# 2_TSAL.net
KiCad netlist of a schematic drawn in Altium Designer
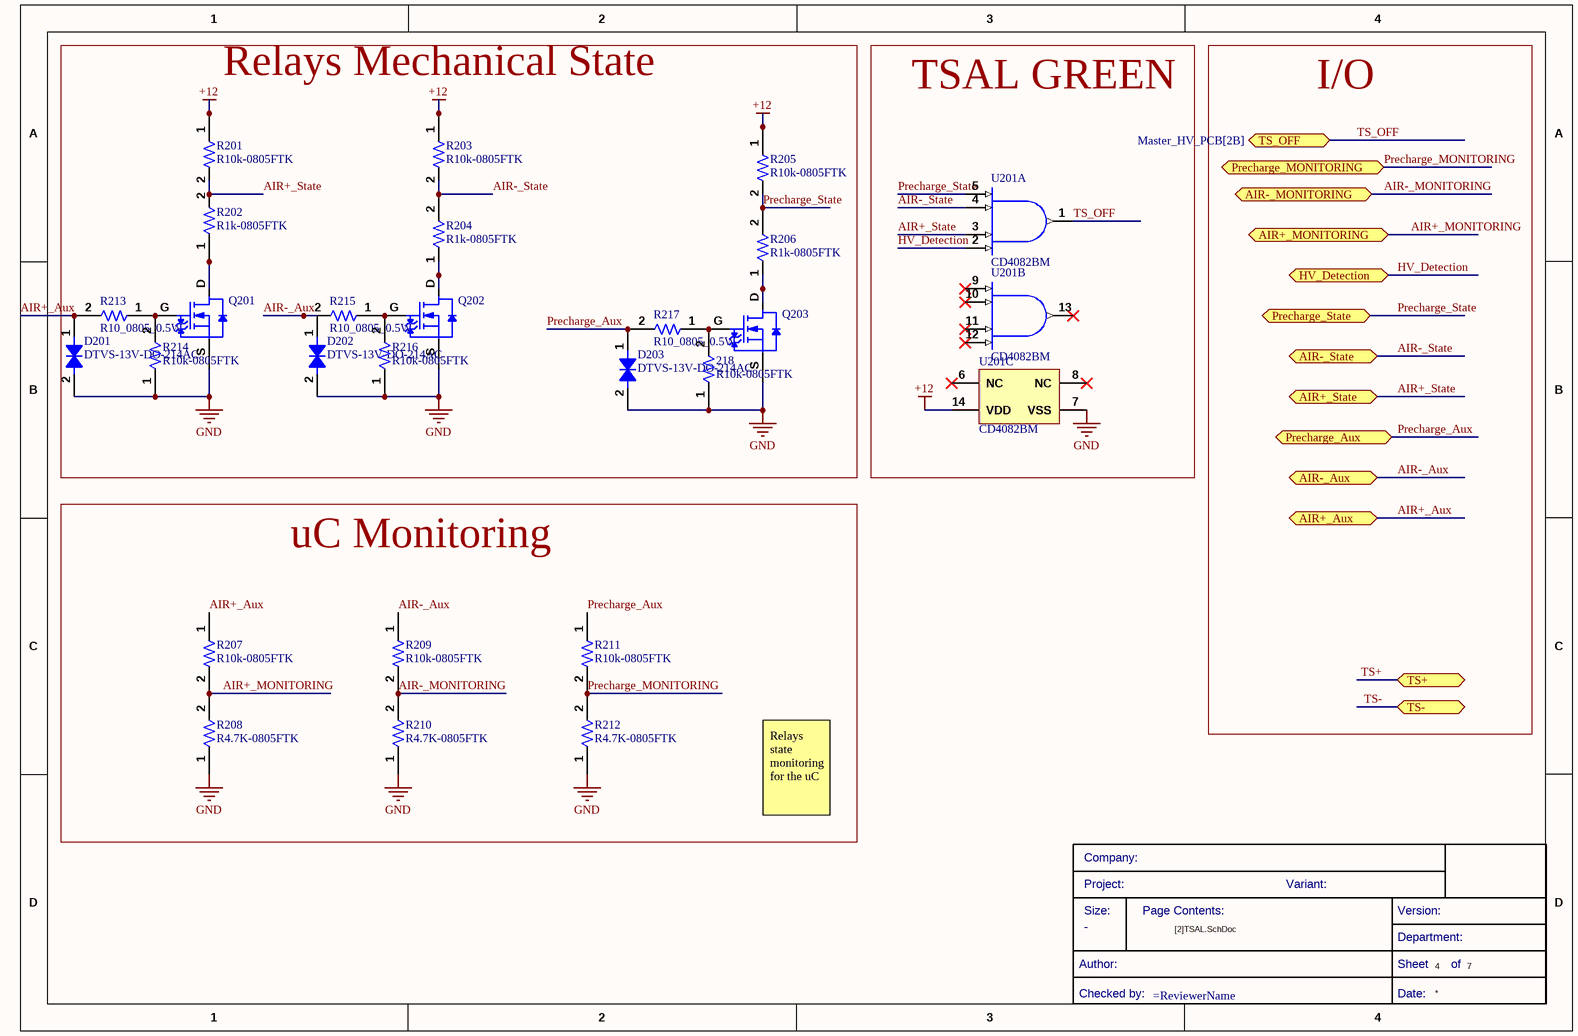
[diagram p0: [2]TSAL.SchDoc]

(export (version "E")
  (design (tool "Eeschema 10.0.6"))
  (components
    (comp (ref "218")
      (value "R10k-0805FTK")
      (footprint "R0805FTK")
      (fields (field (name "TOLERANCE") "5%") (field (name ".CREATOR") "DR"))
      (libsource (lib "EMEA- E-Tech Racing- I'Escola d'Enginyeria de Barcelona Est") (part "R"))
    )
    (comp (ref "D201")
      (value "DTVS-13V-DO-214AC")
      (footprint "DTVS-DO-214AC")
      (description "Tvs Diode, 400W, 13V, Bidir, DO-214AC")
      (fields
        (field (name "MANUFACTURER PART NUMBER") "824501131")
        (field (name "MANUFACTURER") "Wurth Electronics")
        (field (name ".CREATOR") "DO")
      )
      (libsource (lib "EMEA- E-Tech Racing- I'Escola d'Enginyeria de Barcelona Est") (part "DTVS-BD-30k-SOD323"))
    )
    (comp (ref "D202")
      (value "DTVS-13V-DO-214AC")
      (footprint "DTVS-DO-214AC")
      (description "Tvs Diode, 400W, 13V, Bidir, DO-214AC")
      (fields
        (field (name "MANUFACTURER PART NUMBER") "824501131")
        (field (name "MANUFACTURER") "Wurth Electronics")
        (field (name ".CREATOR") "DO")
      )
      (libsource (lib "EMEA- E-Tech Racing- I'Escola d'Enginyeria de Barcelona Est") (part "DTVS-BD-30k-SOD323"))
    )
    (comp (ref "D203")
      (value "DTVS-13V-DO-214AC")
      (footprint "DTVS-DO-214AC")
      (description "Tvs Diode, 400W, 13V, Bidir, DO-214AC")
      (fields
        (field (name "MANUFACTURER PART NUMBER") "824501131")
        (field (name "MANUFACTURER") "Wurth Electronics")
        (field (name ".CREATOR") "DO")
      )
      (libsource (lib "EMEA- E-Tech Racing- I'Escola d'Enginyeria de Barcelona Est") (part "DTVS-BD-30k-SOD323"))
    )
    (comp (ref "Q201")
      (value "SQ2362ES-T1_BE3")
      (footprint "SOT95P245X110-3N")
      (description "Small Signal Field-Effect Transistor")
      (libsource (lib "EMEA- E-Tech Racing- I'Escola d'Enginyeria de Barcelona Est") (part "TRT-NCH-3/35-CPH"))
    )
    (comp (ref "Q202")
      (value "SQ2362ES-T1_BE3")
      (footprint "SOT95P245X110-3N")
      (description "Small Signal Field-Effect Transistor")
      (libsource (lib "EMEA- E-Tech Racing- I'Escola d'Enginyeria de Barcelona Est") (part "TRT-NCH-3/35-CPH"))
    )
    (comp (ref "Q203")
      (value "SQ2362ES-T1_BE3")
      (footprint "SOT95P245X110-3N")
      (description "Small Signal Field-Effect Transistor")
      (libsource (lib "EMEA- E-Tech Racing- I'Escola d'Enginyeria de Barcelona Est") (part "TRT-NCH-3/35-CPH"))
    )
    (comp (ref "R201")
      (value "R10k-0805FTK")
      (footprint "R0805FTK")
      (fields (field (name "TOLERANCE") "5%") (field (name ".CREATOR") "DR"))
      (libsource (lib "EMEA- E-Tech Racing- I'Escola d'Enginyeria de Barcelona Est") (part "R9.09K-1206FTK"))
    )
    (comp (ref "R202")
      (value "R1k-0805FTK")
      (footprint "R0805FTK")
      (description "Res Thick Film 0805 1K Ohm 5% 1/8W ±200ppm/°C Molded SMD SMD Paper Tape on Plastic Reel")
      (fields (field (name "TOLERANCE") "5%") (field (name ".CREATOR") "GP"))
      (libsource (lib "EMEA- E-Tech Racing- I'Escola d'Enginyeria de Barcelona Est") (part "R9.09K-1206FTK"))
    )
    (comp (ref "R203")
      (value "R10k-0805FTK")
      (footprint "R0805FTK")
      (fields (field (name "TOLERANCE") "5%") (field (name ".CREATOR") "DR"))
      (libsource (lib "EMEA- E-Tech Racing- I'Escola d'Enginyeria de Barcelona Est") (part "R9.09K-1206FTK"))
    )
    (comp (ref "R204")
      (value "R1k-0805FTK")
      (footprint "R0805FTK")
      (description "Res Thick Film 0805 1K Ohm 5% 1/8W ±200ppm/°C Molded SMD SMD Paper Tape on Plastic Reel")
      (fields (field (name "TOLERANCE") "5%") (field (name ".CREATOR") "GP"))
      (libsource (lib "EMEA- E-Tech Racing- I'Escola d'Enginyeria de Barcelona Est") (part "R9.09K-1206FTK"))
    )
    (comp (ref "R205")
      (value "R10k-0805FTK")
      (footprint "R0805FTK")
      (fields (field (name "TOLERANCE") "5%") (field (name ".CREATOR") "DR"))
      (libsource (lib "EMEA- E-Tech Racing- I'Escola d'Enginyeria de Barcelona Est") (part "R9.09K-1206FTK"))
    )
    (comp (ref "R206")
      (value "R1k-0805FTK")
      (footprint "R0805FTK")
      (description "Res Thick Film 0805 1K Ohm 5% 1/8W ±200ppm/°C Molded SMD SMD Paper Tape on Plastic Reel")
      (fields (field (name "TOLERANCE") "5%") (field (name ".CREATOR") "GP"))
      (libsource (lib "EMEA- E-Tech Racing- I'Escola d'Enginyeria de Barcelona Est") (part "R9.09K-1206FTK"))
    )
    (comp (ref "R207")
      (value "R10k-0805FTK")
      (footprint "R0805FTK")
      (fields (field (name "TOLERANCE") "5%") (field (name ".CREATOR") "DR"))
      (libsource (lib "EMEA- E-Tech Racing- I'Escola d'Enginyeria de Barcelona Est") (part "R9.09K-1206FTK"))
    )
    (comp (ref "R208")
      (value "R4.7K-0805FTK")
      (footprint "R0805FTK")
      (description "Res Thick Film 0805 4.7K Ohm 5% 1/8W ±200ppm/°C Molded SMD SMD Paper Tape on Plastic Reel")
      (fields (field (name "TOLERANCE") "5%") (field (name ".CREATOR") "DR"))
      (libsource (lib "EMEA- E-Tech Racing- I'Escola d'Enginyeria de Barcelona Est") (part "R9.09K-1206FTK"))
    )
    (comp (ref "R209")
      (value "R10k-0805FTK")
      (footprint "R0805FTK")
      (fields (field (name "TOLERANCE") "5%") (field (name ".CREATOR") "DR"))
      (libsource (lib "EMEA- E-Tech Racing- I'Escola d'Enginyeria de Barcelona Est") (part "R9.09K-1206FTK"))
    )
    (comp (ref "R210")
      (value "R4.7K-0805FTK")
      (footprint "R0805FTK")
      (description "Res Thick Film 0805 4.7K Ohm 5% 1/8W ±200ppm/°C Molded SMD SMD Paper Tape on Plastic Reel")
      (fields (field (name "TOLERANCE") "5%") (field (name ".CREATOR") "DR"))
      (libsource (lib "EMEA- E-Tech Racing- I'Escola d'Enginyeria de Barcelona Est") (part "R9.09K-1206FTK"))
    )
    (comp (ref "R211")
      (value "R10k-0805FTK")
      (footprint "R0805FTK")
      (fields (field (name "TOLERANCE") "5%") (field (name ".CREATOR") "DR"))
      (libsource (lib "EMEA- E-Tech Racing- I'Escola d'Enginyeria de Barcelona Est") (part "R9.09K-1206FTK"))
    )
    (comp (ref "R212")
      (value "R4.7K-0805FTK")
      (footprint "R0805FTK")
      (description "Res Thick Film 0805 4.7K Ohm 5% 1/8W ±200ppm/°C Molded SMD SMD Paper Tape on Plastic Reel")
      (fields (field (name "TOLERANCE") "5%") (field (name ".CREATOR") "DR"))
      (libsource (lib "EMEA- E-Tech Racing- I'Escola d'Enginyeria de Barcelona Est") (part "R9.09K-1206FTK"))
    )
    (comp (ref "R213")
      (value "R10_0805_0.5W")
      (footprint "0805")
      (fields (field (name "TOLERANCE") "1%") (field (name "POWER") "500mW"))
      (libsource (lib "EMEA- E-Tech Racing- I'Escola d'Enginyeria de Barcelona Est") (part "R9.09K-1206FTK"))
    )
    (comp (ref "R214")
      (value "R10k-0805FTK")
      (footprint "R0805FTK")
      (fields (field (name "TOLERANCE") "5%") (field (name ".CREATOR") "DR"))
      (libsource (lib "EMEA- E-Tech Racing- I'Escola d'Enginyeria de Barcelona Est") (part "R"))
    )
    (comp (ref "R215")
      (value "R10_0805_0.5W")
      (footprint "0805")
      (fields (field (name "TOLERANCE") "1%") (field (name "POWER") "500mW"))
      (libsource (lib "EMEA- E-Tech Racing- I'Escola d'Enginyeria de Barcelona Est") (part "R9.09K-1206FTK"))
    )
    (comp (ref "R216")
      (value "R10k-0805FTK")
      (footprint "R0805FTK")
      (fields (field (name "TOLERANCE") "5%") (field (name ".CREATOR") "DR"))
      (libsource (lib "EMEA- E-Tech Racing- I'Escola d'Enginyeria de Barcelona Est") (part "R"))
    )
    (comp (ref "R217")
      (value "R10_0805_0.5W")
      (footprint "0805")
      (fields (field (name "TOLERANCE") "1%") (field (name "POWER") "500mW"))
      (libsource (lib "EMEA- E-Tech Racing- I'Escola d'Enginyeria de Barcelona Est") (part "R9.09K-1206FTK"))
    )
    (comp (ref "U201")
      (value "CD4082BM")
      (footprint "D0014A_N")
      (description "AND Gate, 4000/14000/40000 Series, 2-Func, 4-Input, CMOS, PDSO14")
      (libsource (lib "EMEA- E-Tech Racing- I'Escola d'Enginyeria de Barcelona Est") (part "TI-CD4082B-14"))
    )
  )
  (nets
    (net (code "1") (name "+12") (class "Default")
      (node (ref "R201") (pin "1") (pinfunction "1_1") (pintype "passive"))
      (node (ref "R203") (pin "1") (pinfunction "1_1") (pintype "passive"))
      (node (ref "R205") (pin "1") (pinfunction "1_1") (pintype "passive"))
      (node (ref "U201") (pin "14") (pinfunction "VDD_14") (pintype "power_in"))
    )
    (net (code "2") (name "/AIR+_Aux") (class "Default")
      (node (ref "D201") (pin "1") (pinfunction "1_1") (pintype "passive"))
      (node (ref "R207") (pin "1") (pinfunction "1_1") (pintype "passive"))
      (node (ref "R213") (pin "2") (pinfunction "2_2") (pintype "passive"))
    )
    (net (code "3") (name "/AIR+_MONITORING") (class "Default")
      (node (ref "R207") (pin "2") (pinfunction "2_2") (pintype "passive"))
      (node (ref "R208") (pin "2") (pinfunction "2_2") (pintype "passive"))
    )
    (net (code "4") (name "/AIR+_State") (class "Default")
      (node (ref "R201") (pin "2") (pinfunction "2_2") (pintype "passive"))
      (node (ref "R202") (pin "2") (pinfunction "2_2") (pintype "passive"))
      (node (ref "U201") (pin "3") (pinfunction "C_3") (pintype "input"))
    )
    (net (code "5") (name "/AIR-_Aux") (class "Default")
      (node (ref "D202") (pin "1") (pinfunction "1_1") (pintype "passive"))
      (node (ref "R209") (pin "1") (pinfunction "1_1") (pintype "passive"))
      (node (ref "R215") (pin "2") (pinfunction "2_2") (pintype "passive"))
    )
    (net (code "6") (name "/AIR-_MONITORING") (class "Default")
      (node (ref "R209") (pin "2") (pinfunction "2_2") (pintype "passive"))
      (node (ref "R210") (pin "2") (pinfunction "2_2") (pintype "passive"))
    )
    (net (code "7") (name "/AIR-_State") (class "Default")
      (node (ref "R203") (pin "2") (pinfunction "2_2") (pintype "passive"))
      (node (ref "R204") (pin "2") (pinfunction "2_2") (pintype "passive"))
      (node (ref "U201") (pin "4") (pinfunction "B_4") (pintype "input"))
    )
    (net (code "8") (name "/HV_Detection") (class "Default")
      (node (ref "U201") (pin "2") (pinfunction "D_2") (pintype "input"))
    )
    (net (code "9") (name "/Precharge_Aux") (class "Default")
      (node (ref "D203") (pin "1") (pinfunction "1_1") (pintype "passive"))
      (node (ref "R211") (pin "1") (pinfunction "1_1") (pintype "passive"))
      (node (ref "R217") (pin "2") (pinfunction "2_2") (pintype "passive"))
    )
    (net (code "10") (name "/Precharge_MONITORING") (class "Default")
      (node (ref "R211") (pin "2") (pinfunction "2_2") (pintype "passive"))
      (node (ref "R212") (pin "2") (pinfunction "2_2") (pintype "passive"))
    )
    (net (code "11") (name "/Precharge_State") (class "Default")
      (node (ref "R205") (pin "2") (pinfunction "2_2") (pintype "passive"))
      (node (ref "R206") (pin "2") (pinfunction "2_2") (pintype "passive"))
      (node (ref "U201") (pin "5") (pinfunction "A_5") (pintype "input"))
    )
    (net (code "14") (name "/TS_OFF") (class "Default")
      (node (ref "U201") (pin "1") (pinfunction "J_1") (pintype "output"))
    )
    (net (code "15") (name "GND") (class "Default")
      (node (ref "218") (pin "1") (pinfunction "1_1") (pintype "passive"))
      (node (ref "D201") (pin "2") (pinfunction "2_2") (pintype "passive"))
      (node (ref "D202") (pin "2") (pinfunction "2_2") (pintype "passive"))
      (node (ref "D203") (pin "2") (pinfunction "2_2") (pintype "passive"))
      (node (ref "Q201") (pin "S") (pinfunction "S_S") (pintype "passive"))
      (node (ref "Q202") (pin "S") (pinfunction "S_S") (pintype "passive"))
      (node (ref "Q203") (pin "S") (pinfunction "S_S") (pintype "passive"))
      (node (ref "R208") (pin "1") (pinfunction "1_1") (pintype "passive"))
      (node (ref "R210") (pin "1") (pinfunction "1_1") (pintype "passive"))
      (node (ref "R212") (pin "1") (pinfunction "1_1") (pintype "passive"))
      (node (ref "R214") (pin "1") (pinfunction "1_1") (pintype "passive"))
      (node (ref "R216") (pin "1") (pinfunction "1_1") (pintype "passive"))
      (node (ref "U201") (pin "7") (pinfunction "VSS_7") (pintype "power_in"))
    )
    (net (code "16") (name "Net-(218-Pad2)") (class "Default")
      (node (ref "218") (pin "2") (pinfunction "2_2") (pintype "passive"))
      (node (ref "Q203") (pin "G") (pinfunction "G_G") (pintype "passive"))
      (node (ref "R217") (pin "1") (pinfunction "1_1") (pintype "passive"))
    )
    (net (code "17") (name "Net-(Q201-PadD)") (class "Default")
      (node (ref "Q201") (pin "D") (pinfunction "D_D") (pintype "passive"))
      (node (ref "R202") (pin "1") (pinfunction "1_1") (pintype "passive"))
    )
    (net (code "18") (name "Net-(Q201-PadG)") (class "Default")
      (node (ref "Q201") (pin "G") (pinfunction "G_G") (pintype "passive"))
      (node (ref "R213") (pin "1") (pinfunction "1_1") (pintype "passive"))
      (node (ref "R214") (pin "2") (pinfunction "2_2") (pintype "passive"))
    )
    (net (code "19") (name "Net-(Q202-PadD)") (class "Default")
      (node (ref "Q202") (pin "D") (pinfunction "D_D") (pintype "passive"))
      (node (ref "R204") (pin "1") (pinfunction "1_1") (pintype "passive"))
    )
    (net (code "20") (name "Net-(Q202-PadG)") (class "Default")
      (node (ref "Q202") (pin "G") (pinfunction "G_G") (pintype "passive"))
      (node (ref "R215") (pin "1") (pinfunction "1_1") (pintype "passive"))
      (node (ref "R216") (pin "2") (pinfunction "2_2") (pintype "passive"))
    )
    (net (code "21") (name "Net-(Q203-PadD)") (class "Default")
      (node (ref "Q203") (pin "D") (pinfunction "D_D") (pintype "passive"))
      (node (ref "R206") (pin "1") (pinfunction "1_1") (pintype "passive"))
    )
    (net (code "22") (name "unconnected-(U201B-E-Pad9)") (class "Default")
      (node (ref "U201") (pin "9") (pinfunction "E_9") (pintype "input+no_connect"))
    )
    (net (code "23") (name "unconnected-(U201B-F-Pad10)") (class "Default")
      (node (ref "U201") (pin "10") (pinfunction "F_10") (pintype "input+no_connect"))
    )
    (net (code "24") (name "unconnected-(U201B-G-Pad11)") (class "Default")
      (node (ref "U201") (pin "11") (pinfunction "G_11") (pintype "input+no_connect"))
    )
    (net (code "25") (name "unconnected-(U201B-H-Pad12)") (class "Default")
      (node (ref "U201") (pin "12") (pinfunction "H_12") (pintype "input+no_connect"))
    )
    (net (code "26") (name "unconnected-(U201B-K-Pad13)") (class "Default")
      (node (ref "U201") (pin "13") (pinfunction "K_13") (pintype "output+no_connect"))
    )
    (net (code "27") (name "unconnected-(U201C-NC-Pad6)") (class "Default")
      (node (ref "U201") (pin "6") (pinfunction "NC_6") (pintype "passive+no_connect"))
    )
    (net (code "28") (name "unconnected-(U201C-NC-Pad8)") (class "Default")
      (node (ref "U201") (pin "8") (pinfunction "NC_8") (pintype "passive+no_connect"))
    )
  )
)
